# PIC_Microcontroller_Design.net
KiCad netlist of a schematic drawn in Altium Designer
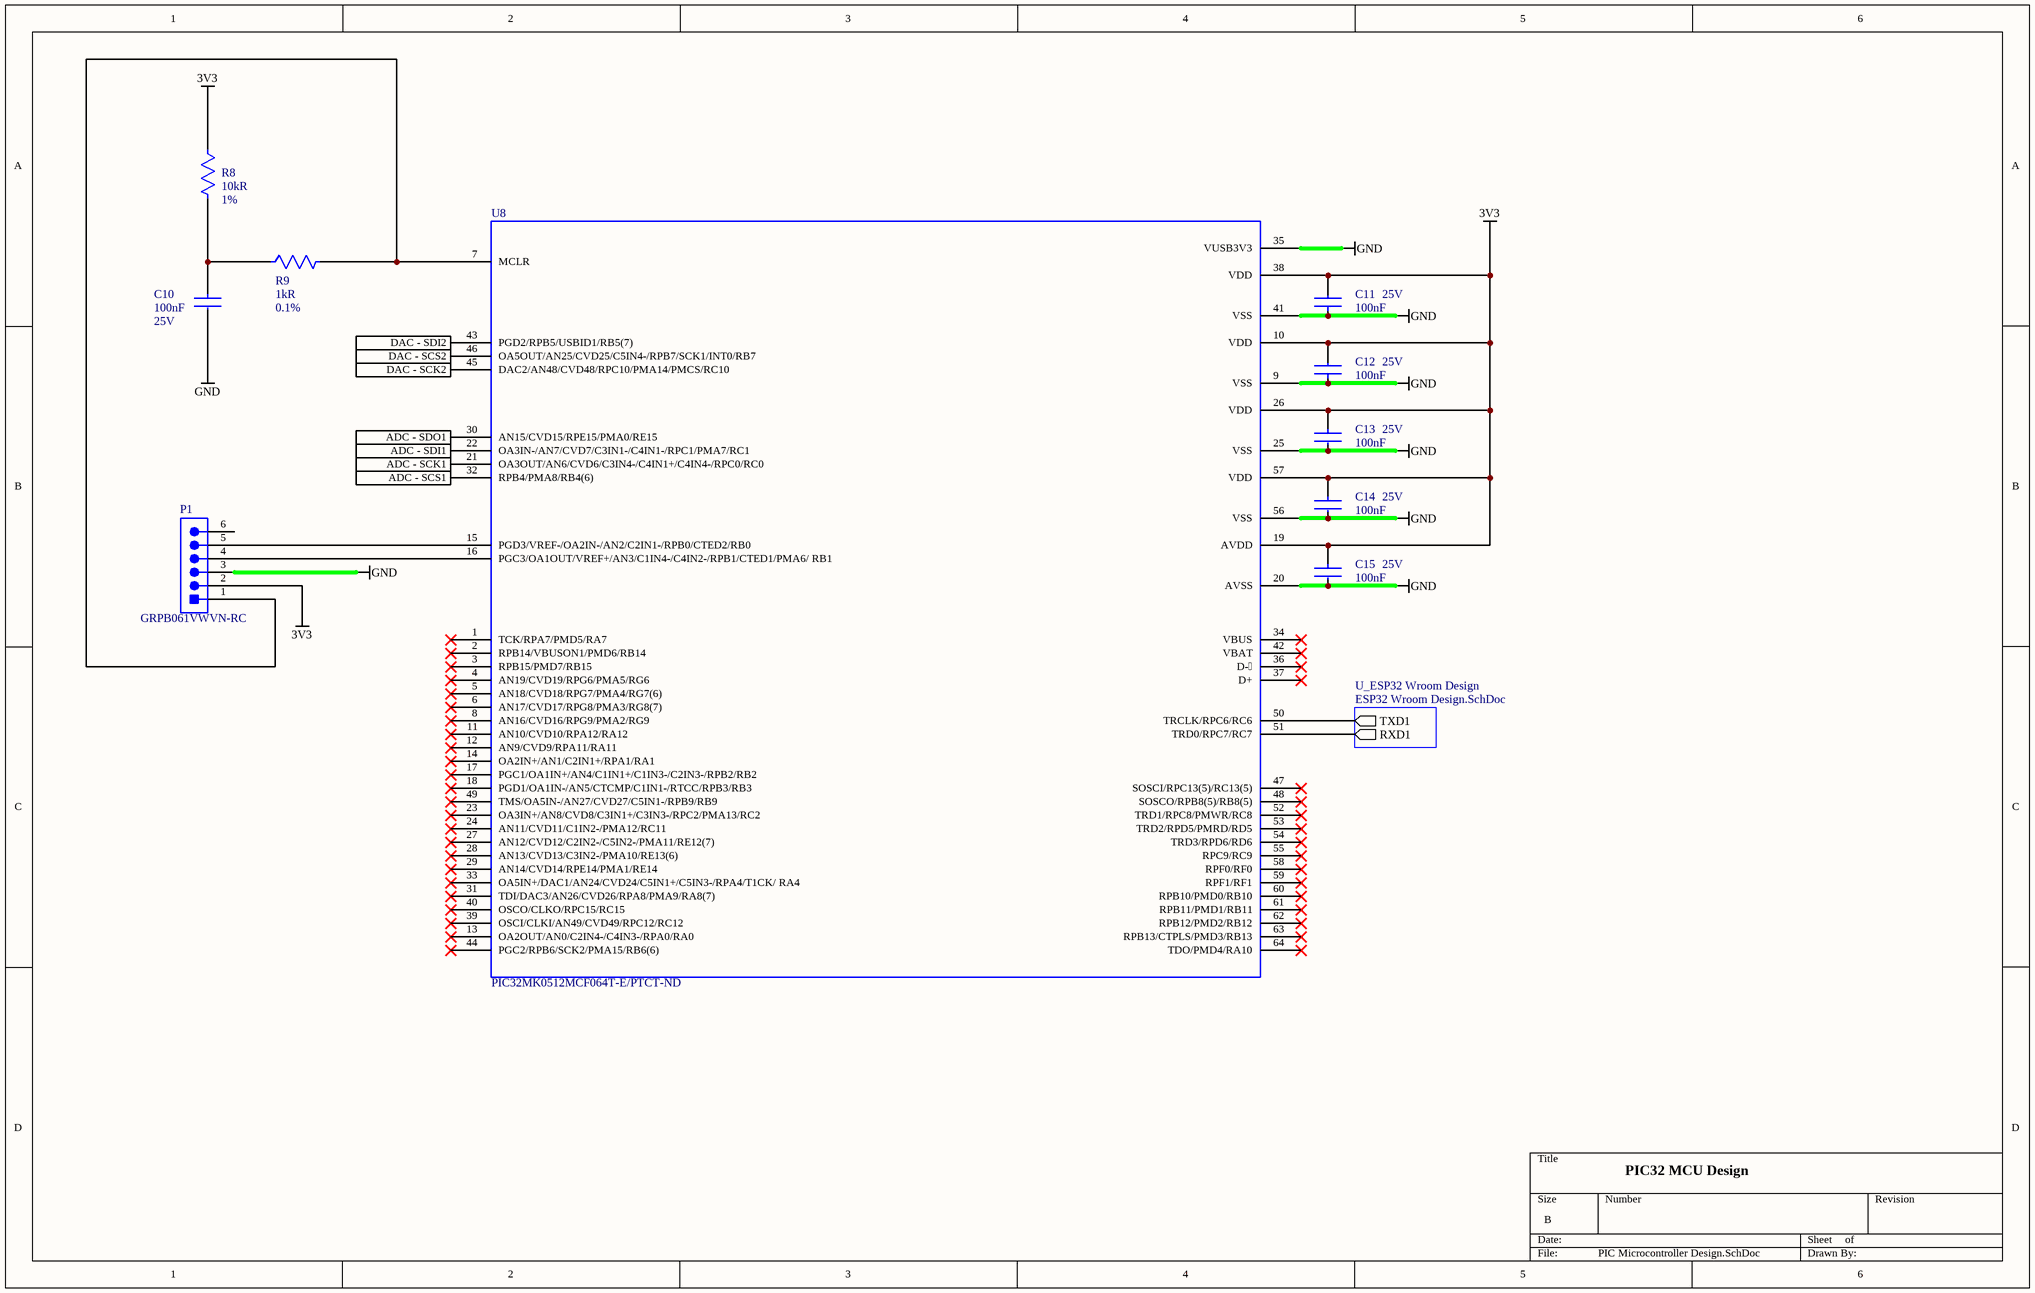
[diagram p0: PIC Microcontroller Design.SchDoc]

(export (version "E")
  (design (tool "Eeschema 10.0.6"))
  (components
    (comp (ref "C10")
      (value "0.1uF")
      (footprint "FP-CL278-IPC_C")
      (description "Cap Ceramic 100nF 25V X5R ±10% SMD 0402 +85°C Paper T/R")
      (fields
        (field (name "VOLTAGE") "25V")
        (field (name "TOLERANCE") "10%")
        (field (name "CAPACITANCE") "100nF")
      )
      (libsource (lib "Altium Content Vault") (part "b4654b650e69147ec39a6b967a45e02"))
    )
    (comp (ref "C11")
      (value "0.1uF")
      (footprint "FP-CL278-IPC_C")
      (description "Cap Ceramic 100nF 25V X5R ±10% SMD 0402 +85°C Paper T/R")
      (fields
        (field (name "VOLTAGE") "25V")
        (field (name "TOLERANCE") "10%")
        (field (name "CAPACITANCE") "100nF")
      )
      (libsource (lib "Altium Content Vault") (part "b4654b650e69147ec39a6b967a45e02"))
    )
    (comp (ref "C12")
      (value "0.1uF")
      (footprint "FP-CL278-IPC_C")
      (description "Cap Ceramic 100nF 25V X5R ±10% SMD 0402 +85°C Paper T/R")
      (fields
        (field (name "VOLTAGE") "25V")
        (field (name "TOLERANCE") "10%")
        (field (name "CAPACITANCE") "100nF")
      )
      (libsource (lib "Altium Content Vault") (part "b4654b650e69147ec39a6b967a45e02"))
    )
    (comp (ref "C13")
      (value "0.1uF")
      (footprint "FP-CL278-IPC_C")
      (description "Cap Ceramic 100nF 25V X5R ±10% SMD 0402 +85°C Paper T/R")
      (fields
        (field (name "VOLTAGE") "25V")
        (field (name "TOLERANCE") "10%")
        (field (name "CAPACITANCE") "100nF")
      )
      (libsource (lib "Altium Content Vault") (part "b4654b650e69147ec39a6b967a45e02"))
    )
    (comp (ref "C14")
      (value "0.1uF")
      (footprint "FP-CL278-IPC_C")
      (description "Cap Ceramic 100nF 25V X5R ±10% SMD 0402 +85°C Paper T/R")
      (fields
        (field (name "VOLTAGE") "25V")
        (field (name "TOLERANCE") "10%")
        (field (name "CAPACITANCE") "100nF")
      )
      (libsource (lib "Altium Content Vault") (part "b4654b650e69147ec39a6b967a45e02"))
    )
    (comp (ref "C15")
      (value "0.1uF")
      (footprint "FP-CL278-IPC_C")
      (description "Cap Ceramic 100nF 25V X5R ±10% SMD 0402 +85°C Paper T/R")
      (fields
        (field (name "VOLTAGE") "25V")
        (field (name "TOLERANCE") "10%")
        (field (name "CAPACITANCE") "100nF")
      )
      (libsource (lib "Altium Content Vault") (part "b4654b650e69147ec39a6b967a45e02"))
    )
    (comp (ref "P1")
      (value "GRPB061VWVN-RC")
      (footprint "SLIN-GRPB061VWVN-RC_V")
      (fields (field (name "MANUFACTURER") "Sullins"))
      (libsource (lib "Altium Content Vault") (part "CN-1P-M-R6"))
    )
    (comp (ref "R8")
      (value "RMCF0201FT10K0")
      (footprint "FP-RMCF0201-IPC_B")
      (description "RES 10K OHM 1% 1/20W 0201")
      (fields (field (name "RESISTANCE") "10kR") (field (name "TOLERANCE") "1%"))
      (libsource (lib "Altium Content Vault") (part "1029c3af85768c4190bb7ad29bc67b5"))
    )
    (comp (ref "R9")
      (value "1k ohm")
      (footprint "FP-RG2012-IPC_B")
      (description "Automotive Metal Thin Film Chip Resistor, 0805, 1kΩ, 0.1%, 25ppm/°C, 0.125W, 150V")
      (fields (field (name "TOLERANCE") "0.1%") (field (name "RESISTANCE") "1kR"))
      (libsource (lib "Altium Content Vault") (part "1029c3af85768c4190bb7ad29bc67b5"))
    )
    (comp (ref "U8")
      (value "PIC32MK0512MCF064T-E/PTCT-ND")
      (footprint "PIC32")
      (libsource (lib "ECEN215LabKit_Library") (part "PIC32MK"))
    )
  )
  (nets
    (net (code "1") (name "/ADC - SCK1") (class "Default")
      (node (ref "U8") (pin "21") (pinfunction "OA3OUT/AN6/CVD6/C3IN4-/C4IN1+/C4IN4-/RPC0/RC0_21") (pintype "passive"))
    )
    (net (code "2") (name "/ADC - SCS1") (class "Default")
      (node (ref "U8") (pin "32") (pinfunction "RPB4/PMA8/RB4(6)_32") (pintype "passive"))
    )
    (net (code "3") (name "/ADC - SDI1") (class "Default")
      (node (ref "U8") (pin "22") (pinfunction "OA3IN-/AN7/CVD7/C3IN1-/C4IN1-/RPC1/PMA7/RC1_22") (pintype "passive"))
    )
    (net (code "4") (name "/ADC - SDO1") (class "Default")
      (node (ref "U8") (pin "30") (pinfunction "AN15/CVD15/RPE15/PMA0/RE15_30") (pintype "passive"))
    )
    (net (code "5") (name "/DAC - SCK2") (class "Default")
      (node (ref "U8") (pin "45") (pinfunction "DAC2/AN48/CVD48/RPC10/PMA14/PMCS/RC10_45") (pintype "passive"))
    )
    (net (code "6") (name "/DAC - SCS2") (class "Default")
      (node (ref "U8") (pin "46") (pinfunction "OA5OUT/AN25/CVD25/C5IN4-/RPB7/SCK1/INT0/RB7_46") (pintype "passive"))
    )
    (net (code "7") (name "/DAC - SDI2") (class "Default")
      (node (ref "U8") (pin "43") (pinfunction "PGD2/RPB5/USBID1/RB5(7)_43") (pintype "passive"))
    )
    (net (code "8") (name "/RXD1") (class "Default")
      (node (ref "U8") (pin "51") (pinfunction "TRD0/RPC7/RC7_51") (pintype "passive"))
    )
    (net (code "9") (name "/TXD1") (class "Default")
      (node (ref "U8") (pin "50") (pinfunction "TRCLK/RPC6/RC6_50") (pintype "passive"))
    )
    (net (code "10") (name "3V3") (class "Default")
      (node (ref "C11") (pin "2") (pinfunction "2_2") (pintype "passive"))
      (node (ref "C12") (pin "2") (pinfunction "2_2") (pintype "passive"))
      (node (ref "C13") (pin "1") (pinfunction "1_1") (pintype "passive"))
      (node (ref "C14") (pin "1") (pinfunction "1_1") (pintype "passive"))
      (node (ref "C15") (pin "1") (pinfunction "1_1") (pintype "passive"))
      (node (ref "P1") (pin "2") (pinfunction "2_2") (pintype "passive"))
      (node (ref "R8") (pin "1") (pinfunction "1_1") (pintype "passive"))
      (node (ref "U8") (pin "10") (pinfunction "VDD_10") (pintype "power_in"))
      (node (ref "U8") (pin "19") (pinfunction "AVDD_19") (pintype "power_in"))
      (node (ref "U8") (pin "26") (pinfunction "VDD_26") (pintype "power_in"))
      (node (ref "U8") (pin "38") (pinfunction "VDD_38") (pintype "power_in"))
      (node (ref "U8") (pin "57") (pinfunction "VDD_57") (pintype "power_in"))
    )
    (net (code "11") (name "GND") (class "Default")
      (node (ref "C10") (pin "2") (pinfunction "2_2") (pintype "passive"))
      (node (ref "C11") (pin "1") (pinfunction "1_1") (pintype "passive"))
      (node (ref "C12") (pin "1") (pinfunction "1_1") (pintype "passive"))
      (node (ref "C13") (pin "2") (pinfunction "2_2") (pintype "passive"))
      (node (ref "C14") (pin "2") (pinfunction "2_2") (pintype "passive"))
      (node (ref "C15") (pin "2") (pinfunction "2_2") (pintype "passive"))
      (node (ref "P1") (pin "3") (pinfunction "3_3") (pintype "passive"))
      (node (ref "U8") (pin "20") (pinfunction "AVSS_20") (pintype "power_in"))
      (node (ref "U8") (pin "25") (pinfunction "VSS_25") (pintype "power_in"))
      (node (ref "U8") (pin "35") (pinfunction "VUSB3V3_35") (pintype "power_in"))
      (node (ref "U8") (pin "41") (pinfunction "VSS_41") (pintype "power_in"))
      (node (ref "U8") (pin "56") (pinfunction "VSS_56") (pintype "power_in"))
      (node (ref "U8") (pin "9") (pinfunction "VSS_9") (pintype "power_in"))
    )
    (net (code "12") (name "Net-(C10-Pad1)") (class "Default")
      (node (ref "C10") (pin "1") (pinfunction "1_1") (pintype "passive"))
      (node (ref "R8") (pin "2") (pinfunction "2_2") (pintype "passive"))
      (node (ref "R9") (pin "1") (pinfunction "1_1") (pintype "passive"))
    )
    (net (code "13") (name "Net-(U8-MCLR)") (class "Default")
      (node (ref "P1") (pin "1") (pinfunction "1_1") (pintype "passive"))
      (node (ref "R9") (pin "2") (pinfunction "2_2") (pintype "passive"))
      (node (ref "U8") (pin "7") (pinfunction "MCLR_7") (pintype "passive"))
    )
    (net (code "14") (name "Net-(U8-PGC3{slash}OA1OUT{slash}VREF+{slash}AN3{slash}C1IN4-{slash}C4IN2-{slash}RPB1{slash}CTED1{slash}PMA6{slash}_RB1)") (class "Default")
      (node (ref "P1") (pin "4") (pinfunction "4_4") (pintype "passive"))
      (node (ref "U8") (pin "16") (pinfunction "PGC3/OA1OUT/VREF+/AN3/C1IN4-/C4IN2-/RPB1/CTED1/PMA6/_RB1_16") (pintype "passive"))
    )
    (net (code "15") (name "Net-(U8-PGD3{slash}VREF-{slash}OA2IN-{slash}AN2{slash}C2IN1-{slash}RPB0{slash}CTED2{slash}RB0)") (class "Default")
      (node (ref "P1") (pin "5") (pinfunction "5_5") (pintype "passive"))
      (node (ref "U8") (pin "15") (pinfunction "PGD3/VREF-/OA2IN-/AN2/C2IN1-/RPB0/CTED2/RB0_15") (pintype "passive"))
    )
    (net (code "16") (name "unconnected-(P1-Pad6)") (class "Default")
      (node (ref "P1") (pin "6") (pinfunction "6_6") (pintype "passive"))
    )
    (net (code "17") (name "unconnected-(U8-AN9{slash}CVD9{slash}RPA11{slash}RA11-Pad12)") (class "Default")
      (node (ref "U8") (pin "12") (pinfunction "AN9/CVD9/RPA11/RA11_12") (pintype "passive+no_connect"))
    )
    (net (code "18") (name "unconnected-(U8-AN10{slash}CVD10{slash}RPA12{slash}RA12-Pad11)") (class "Default")
      (node (ref "U8") (pin "11") (pinfunction "AN10/CVD10/RPA12/RA12_11") (pintype "passive+no_connect"))
    )
    (net (code "19") (name "unconnected-(U8-AN11{slash}CVD11{slash}C1IN2-{slash}PMA12{slash}RC11-Pad24)") (class "Default")
      (node (ref "U8") (pin "24") (pinfunction "AN11/CVD11/C1IN2-/PMA12/RC11_24") (pintype "passive+no_connect"))
    )
    (net (code "20") (name "unconnected-(U8-AN12{slash}CVD12{slash}C2IN2-{slash}C5IN2-{slash}PMA11{slash}RE12(7)-Pad27)") (class "Default")
      (node (ref "U8") (pin "27") (pinfunction "AN12/CVD12/C2IN2-/C5IN2-/PMA11/RE12(7)_27") (pintype "passive+no_connect"))
    )
    (net (code "21") (name "unconnected-(U8-AN13{slash}CVD13{slash}C3IN2-{slash}PMA10{slash}RE13(6)-Pad28)") (class "Default")
      (node (ref "U8") (pin "28") (pinfunction "AN13/CVD13/C3IN2-/PMA10/RE13(6)_28") (pintype "passive+no_connect"))
    )
    (net (code "22") (name "unconnected-(U8-AN14{slash}CVD14{slash}RPE14{slash}PMA1{slash}RE14-Pad29)") (class "Default")
      (node (ref "U8") (pin "29") (pinfunction "AN14/CVD14/RPE14/PMA1/RE14_29") (pintype "passive+no_connect"))
    )
    (net (code "23") (name "unconnected-(U8-AN16{slash}CVD16{slash}RPG9{slash}PMA2{slash}RG9-Pad8)") (class "Default")
      (node (ref "U8") (pin "8") (pinfunction "AN16/CVD16/RPG9/PMA2/RG9_8") (pintype "passive+no_connect"))
    )
    (net (code "24") (name "unconnected-(U8-AN17{slash}CVD17{slash}RPG8{slash}PMA3{slash}RG8(7)-Pad6)") (class "Default")
      (node (ref "U8") (pin "6") (pinfunction "AN17/CVD17/RPG8/PMA3/RG8(7)_6") (pintype "passive+no_connect"))
    )
    (net (code "25") (name "unconnected-(U8-AN18{slash}CVD18{slash}RPG7{slash}PMA4{slash}RG7(6)-Pad5)") (class "Default")
      (node (ref "U8") (pin "5") (pinfunction "AN18/CVD18/RPG7/PMA4/RG7(6)_5") (pintype "passive+no_connect"))
    )
    (net (code "26") (name "unconnected-(U8-AN19{slash}CVD19{slash}RPG6{slash}PMA5{slash}RG6-Pad4)") (class "Default")
      (node (ref "U8") (pin "4") (pinfunction "AN19/CVD19/RPG6/PMA5/RG6_4") (pintype "passive+no_connect"))
    )
    (net (code "27") (name "unconnected-(U8-D+-Pad37)") (class "Default")
      (node (ref "U8") (pin "37") (pinfunction "D+_37") (pintype "passive+no_connect"))
    )
    (net (code "28") (name "unconnected-(U8-D--Pad36)") (class "Default")
      (node (ref "U8") (pin "36") (pinfunction "D-_36") (pintype "passive+no_connect"))
    )
    (net (code "29") (name "unconnected-(U8-OA2IN+{slash}AN1{slash}C2IN1+{slash}RPA1{slash}RA1-Pad14)") (class "Default")
      (node (ref "U8") (pin "14") (pinfunction "OA2IN+/AN1/C2IN1+/RPA1/RA1_14") (pintype "passive+no_connect"))
    )
    (net (code "30") (name "unconnected-(U8-OA2OUT{slash}AN0{slash}C2IN4-{slash}C4IN3-{slash}RPA0{slash}RA0-Pad13)") (class "Default")
      (node (ref "U8") (pin "13") (pinfunction "OA2OUT/AN0/C2IN4-/C4IN3-/RPA0/RA0_13") (pintype "passive+no_connect"))
    )
    (net (code "31") (name "unconnected-(U8-OA3IN+{slash}AN8{slash}CVD8{slash}C3IN1+{slash}C3IN3-{slash}RPC2{slash}PMA13{slash}RC2-Pad23)") (class "Default")
      (node (ref "U8") (pin "23") (pinfunction "OA3IN+/AN8/CVD8/C3IN1+/C3IN3-/RPC2/PMA13/RC2_23") (pintype "passive+no_connect"))
    )
    (net (code "32") (name "unconnected-(U8-OA5IN+{slash}DAC1{slash}AN24{slash}CVD24{slash}C5IN1+{slash}C5IN3-{slash}RPA4{slash}T1CK{slash}_RA4-Pad33)") (class "Default")
      (node (ref "U8") (pin "33") (pinfunction "OA5IN+/DAC1/AN24/CVD24/C5IN1+/C5IN3-/RPA4/T1CK/_RA4_33") (pintype "passive+no_connect"))
    )
    (net (code "33") (name "unconnected-(U8-OSCI{slash}CLKI{slash}AN49{slash}CVD49{slash}RPC12{slash}RC12-Pad39)") (class "Default")
      (node (ref "U8") (pin "39") (pinfunction "OSCI/CLKI/AN49/CVD49/RPC12/RC12_39") (pintype "passive+no_connect"))
    )
    (net (code "34") (name "unconnected-(U8-OSCO{slash}CLKO{slash}RPC15{slash}RC15-Pad40)") (class "Default")
      (node (ref "U8") (pin "40") (pinfunction "OSCO/CLKO/RPC15/RC15_40") (pintype "passive+no_connect"))
    )
    (net (code "35") (name "unconnected-(U8-PGC1{slash}OA1IN+{slash}AN4{slash}C1IN1+{slash}C1IN3-{slash}C2IN3-{slash}RPB2{slash}RB2-Pad17)") (class "Default")
      (node (ref "U8") (pin "17") (pinfunction "PGC1/OA1IN+/AN4/C1IN1+/C1IN3-/C2IN3-/RPB2/RB2_17") (pintype "passive+no_connect"))
    )
    (net (code "36") (name "unconnected-(U8-PGC2{slash}RPB6{slash}SCK2{slash}PMA15{slash}RB6(6)-Pad44)") (class "Default")
      (node (ref "U8") (pin "44") (pinfunction "PGC2/RPB6/SCK2/PMA15/RB6(6)_44") (pintype "passive+no_connect"))
    )
    (net (code "37") (name "unconnected-(U8-PGD1{slash}OA1IN-{slash}AN5{slash}CTCMP{slash}C1IN1-{slash}RTCC{slash}RPB3{slash}RB3-Pad18)") (class "Default")
      (node (ref "U8") (pin "18") (pinfunction "PGD1/OA1IN-/AN5/CTCMP/C1IN1-/RTCC/RPB3/RB3_18") (pintype "passive+no_connect"))
    )
    (net (code "38") (name "unconnected-(U8-RPB10{slash}PMD0{slash}RB10-Pad60)") (class "Default")
      (node (ref "U8") (pin "60") (pinfunction "RPB10/PMD0/RB10_60") (pintype "passive+no_connect"))
    )
    (net (code "39") (name "unconnected-(U8-RPB11{slash}PMD1{slash}RB11-Pad61)") (class "Default")
      (node (ref "U8") (pin "61") (pinfunction "RPB11/PMD1/RB11_61") (pintype "passive+no_connect"))
    )
    (net (code "40") (name "unconnected-(U8-RPB12{slash}PMD2{slash}RB12-Pad62)") (class "Default")
      (node (ref "U8") (pin "62") (pinfunction "RPB12/PMD2/RB12_62") (pintype "passive+no_connect"))
    )
    (net (code "41") (name "unconnected-(U8-RPB13{slash}CTPLS{slash}PMD3{slash}RB13-Pad63)") (class "Default")
      (node (ref "U8") (pin "63") (pinfunction "RPB13/CTPLS/PMD3/RB13_63") (pintype "passive+no_connect"))
    )
    (net (code "42") (name "unconnected-(U8-RPB14{slash}VBUSON1{slash}PMD6{slash}RB14-Pad2)") (class "Default")
      (node (ref "U8") (pin "2") (pinfunction "RPB14/VBUSON1/PMD6/RB14_2") (pintype "passive+no_connect"))
    )
    (net (code "43") (name "unconnected-(U8-RPB15{slash}PMD7{slash}RB15-Pad3)") (class "Default")
      (node (ref "U8") (pin "3") (pinfunction "RPB15/PMD7/RB15_3") (pintype "passive+no_connect"))
    )
    (net (code "44") (name "unconnected-(U8-RPC9{slash}RC9-Pad55)") (class "Default")
      (node (ref "U8") (pin "55") (pinfunction "RPC9/RC9_55") (pintype "passive+no_connect"))
    )
    (net (code "45") (name "unconnected-(U8-RPF0{slash}RF0-Pad58)") (class "Default")
      (node (ref "U8") (pin "58") (pinfunction "RPF0/RF0_58") (pintype "passive+no_connect"))
    )
    (net (code "46") (name "unconnected-(U8-RPF1{slash}RF1-Pad59)") (class "Default")
      (node (ref "U8") (pin "59") (pinfunction "RPF1/RF1_59") (pintype "passive+no_connect"))
    )
    (net (code "47") (name "unconnected-(U8-SOSCI{slash}RPC13(5){slash}RC13(5)-Pad47)") (class "Default")
      (node (ref "U8") (pin "47") (pinfunction "SOSCI/RPC13(5)/RC13(5)_47") (pintype "passive+no_connect"))
    )
    (net (code "48") (name "unconnected-(U8-SOSCO{slash}RPB8(5){slash}RB8(5)-Pad48)") (class "Default")
      (node (ref "U8") (pin "48") (pinfunction "SOSCO/RPB8(5)/RB8(5)_48") (pintype "passive+no_connect"))
    )
    (net (code "49") (name "unconnected-(U8-TCK{slash}RPA7{slash}PMD5{slash}RA7-Pad1)") (class "Default")
      (node (ref "U8") (pin "1") (pinfunction "TCK/RPA7/PMD5/RA7_1") (pintype "passive+no_connect"))
    )
    (net (code "50") (name "unconnected-(U8-TDI{slash}DAC3{slash}AN26{slash}CVD26{slash}RPA8{slash}PMA9{slash}RA8(7)-Pad31)") (class "Default")
      (node (ref "U8") (pin "31") (pinfunction "TDI/DAC3/AN26/CVD26/RPA8/PMA9/RA8(7)_31") (pintype "passive+no_connect"))
    )
    (net (code "51") (name "unconnected-(U8-TDO{slash}PMD4{slash}RA10-Pad64)") (class "Default")
      (node (ref "U8") (pin "64") (pinfunction "TDO/PMD4/RA10_64") (pintype "passive+no_connect"))
    )
    (net (code "52") (name "unconnected-(U8-TMS{slash}OA5IN-{slash}AN27{slash}CVD27{slash}C5IN1-{slash}RPB9{slash}RB9-Pad49)") (class "Default")
      (node (ref "U8") (pin "49") (pinfunction "TMS/OA5IN-/AN27/CVD27/C5IN1-/RPB9/RB9_49") (pintype "passive+no_connect"))
    )
    (net (code "53") (name "unconnected-(U8-TRD1{slash}RPC8{slash}PMWR{slash}RC8-Pad52)") (class "Default")
      (node (ref "U8") (pin "52") (pinfunction "TRD1/RPC8/PMWR/RC8_52") (pintype "passive+no_connect"))
    )
    (net (code "54") (name "unconnected-(U8-TRD2{slash}RPD5{slash}PMRD{slash}RD5-Pad53)") (class "Default")
      (node (ref "U8") (pin "53") (pinfunction "TRD2/RPD5/PMRD/RD5_53") (pintype "passive+no_connect"))
    )
    (net (code "55") (name "unconnected-(U8-TRD3{slash}RPD6{slash}RD6-Pad54)") (class "Default")
      (node (ref "U8") (pin "54") (pinfunction "TRD3/RPD6/RD6_54") (pintype "passive+no_connect"))
    )
    (net (code "56") (name "unconnected-(U8-VBAT-Pad42)") (class "Default")
      (node (ref "U8") (pin "42") (pinfunction "VBAT_42") (pintype "passive+no_connect"))
    )
    (net (code "57") (name "unconnected-(U8-VBUS-Pad34)") (class "Default")
      (node (ref "U8") (pin "34") (pinfunction "VBUS_34") (pintype "passive+no_connect"))
    )
  )
)
